# stompadapter_10-17-20.net
KiCad netlist of a schematic drawn in EAGLE
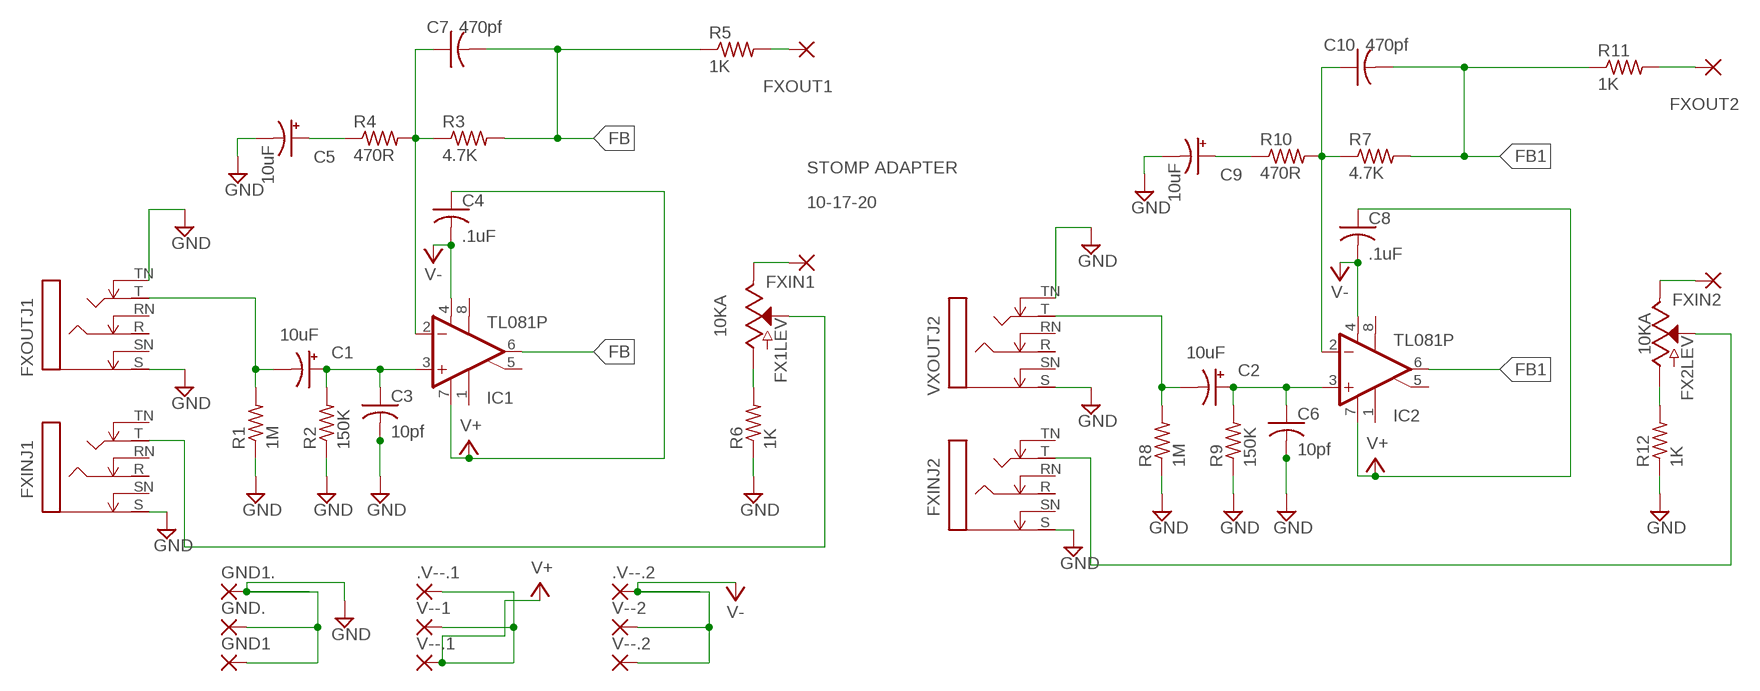
[diagram p0: schematic, sheet 1]

(export (version "E")
  (design (tool "Eeschema 10.0.6"))
  (components
    (comp (ref ".V--.1")
      (value "3,17/1,3")
      (footprint "eagle-import:3,17_1,3")
      (libsource (lib "eagle-import") (part "3,17/1,3"))
    )
    (comp (ref ".V--.2")
      (value "3,17/1,3")
      (footprint "eagle-import:3,17_1,3")
      (libsource (lib "eagle-import") (part "3,17/1,3"))
    )
    (comp (ref "C1")
      (value "10uF")
      (footprint "eagle-import:E5-6")
      (libsource (lib "eagle-import") (part "CPOL-USE5-6"))
    )
    (comp (ref "C2")
      (value "10uF")
      (footprint "eagle-import:E5-6")
      (libsource (lib "eagle-import") (part "CPOL-USE5-6"))
    )
    (comp (ref "C3")
      (value "10pf")
      (footprint "eagle-import:C050-025X075")
      (libsource (lib "eagle-import") (part "C-US050-025X075"))
    )
    (comp (ref "C4")
      (value ".1uF")
      (footprint "eagle-import:C025-025X050")
      (libsource (lib "eagle-import") (part "adafruit_420_C-US025-025X050"))
    )
    (comp (ref "C5")
      (value "10uF")
      (footprint "eagle-import:E5-6")
      (libsource (lib "eagle-import") (part "CPOL-USE5-6"))
    )
    (comp (ref "C6")
      (value "10pf")
      (footprint "eagle-import:C050-025X075")
      (libsource (lib "eagle-import") (part "C-US050-025X075"))
    )
    (comp (ref "C7")
      (value "470pf")
      (footprint "eagle-import:C050-025X075")
      (libsource (lib "eagle-import") (part "C-US050-025X075"))
    )
    (comp (ref "C8")
      (value ".1uF")
      (footprint "eagle-import:C025-025X050")
      (libsource (lib "eagle-import") (part "adafruit_420_C-US025-025X050"))
    )
    (comp (ref "C9")
      (value "10uF")
      (footprint "eagle-import:E5-6")
      (libsource (lib "eagle-import") (part "CPOL-USE5-6"))
    )
    (comp (ref "C10")
      (value "470pf")
      (footprint "eagle-import:C050-025X075")
      (libsource (lib "eagle-import") (part "C-US050-025X075"))
    )
    (comp (ref "FX1LEV")
      (value "10KA")
      (footprint "eagle-import:POT-PTH-ALPS-KIT")
      (libsource (lib "eagle-import") (part "POTENTIOMETER-PTH-9MM-1/20W-20%-KIT"))
    )
    (comp (ref "FX2LEV")
      (value "10KA")
      (footprint "eagle-import:POT-PTH-ALPS-KIT")
      (libsource (lib "eagle-import") (part "POTENTIOMETER-PTH-9MM-1/20W-20%-KIT"))
    )
    (comp (ref "FXIN1")
      (value "3,17/1,3")
      (footprint "eagle-import:3,17_1,3")
      (libsource (lib "eagle-import") (part "wirepad_412_3,17/1,3"))
    )
    (comp (ref "FXIN2")
      (value "3,17/1,3")
      (footprint "eagle-import:3,17_1,3")
      (libsource (lib "eagle-import") (part "wirepad_412_3,17/1,3"))
    )
    (comp (ref "FXINJ1")
      (value "NEUTRIXNMJ6HCD2")
      (footprint "eagle-import:NMJ6HCD2-LARGEPINS")
      (libsource (lib "eagle-import") (part "NEUTRIXNMJ6HCD2"))
    )
    (comp (ref "FXINJ2")
      (value "NEUTRIXNMJ6HCD2")
      (footprint "eagle-import:NMJ6HCD2-LARGEPINS")
      (libsource (lib "eagle-import") (part "NEUTRIXNMJ6HCD2"))
    )
    (comp (ref "FXOUT1")
      (value "3,17/1,3")
      (footprint "eagle-import:3,17_1,3")
      (libsource (lib "eagle-import") (part "wirepad_412_3,17/1,3"))
    )
    (comp (ref "FXOUT2")
      (value "3,17/1,3")
      (footprint "eagle-import:3,17_1,3")
      (libsource (lib "eagle-import") (part "wirepad_412_3,17/1,3"))
    )
    (comp (ref "FXOUTJ1")
      (value "NEUTRIXNMJ6HCD2")
      (footprint "eagle-import:NMJ6HCD2-LARGEPINS")
      (libsource (lib "eagle-import") (part "NEUTRIXNMJ6HCD2"))
    )
    (comp (ref "GND.")
      (value "3,17/1,3")
      (footprint "eagle-import:3,17_1,3")
      (libsource (lib "eagle-import") (part "3,17/1,3"))
    )
    (comp (ref "GND1")
      (value "3,17/1,3")
      (footprint "eagle-import:3,17_1,3")
      (libsource (lib "eagle-import") (part "3,17/1,3"))
    )
    (comp (ref "GND1.")
      (value "3,17/1,3")
      (footprint "eagle-import:3,17_1,3")
      (libsource (lib "eagle-import") (part "3,17/1,3"))
    )
    (comp (ref "IC1")
      (value "TL081P")
      (footprint "eagle-import:DIL08")
      (libsource (lib "eagle-import") (part "TL081P"))
    )
    (comp (ref "IC2")
      (value "TL081P")
      (footprint "eagle-import:DIL08")
      (libsource (lib "eagle-import") (part "TL081P"))
    )
    (comp (ref "R1")
      (value "1M")
      (footprint "eagle-import:0204_7")
      (libsource (lib "eagle-import") (part "R-US_0204/7"))
    )
    (comp (ref "R2")
      (value "150K")
      (footprint "eagle-import:0204_7")
      (libsource (lib "eagle-import") (part "R-US_0204/7"))
    )
    (comp (ref "R3")
      (value "4.7K")
      (footprint "eagle-import:0204_7")
      (libsource (lib "eagle-import") (part "R-US_0204/7"))
    )
    (comp (ref "R4")
      (value "470R")
      (footprint "eagle-import:0204_7")
      (libsource (lib "eagle-import") (part "R-US_0204/7"))
    )
    (comp (ref "R5")
      (value "1K")
      (footprint "eagle-import:0204_7")
      (libsource (lib "eagle-import") (part "R-US_0204/7"))
    )
    (comp (ref "R6")
      (value "1K")
      (footprint "eagle-import:0204_7")
      (libsource (lib "eagle-import") (part "R-US_0204/7"))
    )
    (comp (ref "R7")
      (value "4.7K")
      (footprint "eagle-import:0204_7")
      (libsource (lib "eagle-import") (part "R-US_0204/7"))
    )
    (comp (ref "R8")
      (value "1M")
      (footprint "eagle-import:0204_7")
      (libsource (lib "eagle-import") (part "R-US_0204/7"))
    )
    (comp (ref "R9")
      (value "150K")
      (footprint "eagle-import:0204_7")
      (libsource (lib "eagle-import") (part "R-US_0204/7"))
    )
    (comp (ref "R10")
      (value "470R")
      (footprint "eagle-import:0204_7")
      (libsource (lib "eagle-import") (part "R-US_0204/7"))
    )
    (comp (ref "R11")
      (value "1K")
      (footprint "eagle-import:0204_7")
      (libsource (lib "eagle-import") (part "R-US_0204/7"))
    )
    (comp (ref "R12")
      (value "1K")
      (footprint "eagle-import:0204_7")
      (libsource (lib "eagle-import") (part "R-US_0204/7"))
    )
    (comp (ref "V--.1")
      (value "3,17/1,3")
      (footprint "eagle-import:3,17_1,3")
      (libsource (lib "eagle-import") (part "3,17/1,3"))
    )
    (comp (ref "V--.2")
      (value "3,17/1,3")
      (footprint "eagle-import:3,17_1,3")
      (libsource (lib "eagle-import") (part "3,17/1,3"))
    )
    (comp (ref "V--1")
      (value "3,17/1,3")
      (footprint "eagle-import:3,17_1,3")
      (libsource (lib "eagle-import") (part "3,17/1,3"))
    )
    (comp (ref "V--2")
      (value "3,17/1,3")
      (footprint "eagle-import:3,17_1,3")
      (libsource (lib "eagle-import") (part "3,17/1,3"))
    )
    (comp (ref "VXOUTJ2")
      (value "NEUTRIXNMJ6HCD2")
      (footprint "eagle-import:NMJ6HCD2-LARGEPINS")
      (libsource (lib "eagle-import") (part "NEUTRIXNMJ6HCD2"))
    )
  )
  (nets
    (net (code "1") (name "FB") (class "Default")
      (node (ref "C7") (pin "2") (pinfunction "2_2") (pintype "passive"))
      (node (ref "IC1") (pin "6") (pinfunction "OUT_6") (pintype "output"))
      (node (ref "R3") (pin "2") (pinfunction "2_2") (pintype "passive"))
      (node (ref "R5") (pin "1") (pinfunction "1_1") (pintype "passive"))
    )
    (net (code "2") (name "FB1") (class "Default")
      (node (ref "C10") (pin "2") (pinfunction "2_2") (pintype "passive"))
      (node (ref "IC2") (pin "6") (pinfunction "OUT_6") (pintype "output"))
      (node (ref "R11") (pin "1") (pinfunction "1_1") (pintype "passive"))
      (node (ref "R7") (pin "2") (pinfunction "2_2") (pintype "passive"))
    )
    (net (code "3") (name "GND") (class "Default")
      (node (ref "C3") (pin "2") (pinfunction "2_2") (pintype "passive"))
      (node (ref "C5") (pin "-") (pinfunction "-_-") (pintype "passive"))
      (node (ref "C6") (pin "2") (pinfunction "2_2") (pintype "passive"))
      (node (ref "C9") (pin "-") (pinfunction "-_-") (pintype "passive"))
      (node (ref "FXINJ1") (pin "S") (pinfunction "S_S") (pintype "passive"))
      (node (ref "FXINJ2") (pin "S") (pinfunction "S_S") (pintype "passive"))
      (node (ref "FXOUTJ1") (pin "S") (pinfunction "S_S") (pintype "passive"))
      (node (ref "FXOUTJ1") (pin "TN") (pinfunction "TN_TN") (pintype "passive"))
      (node (ref "GND.") (pin "1") (pinfunction "P_1") (pintype "passive"))
      (node (ref "GND1") (pin "1") (pinfunction "P_1") (pintype "passive"))
      (node (ref "GND1.") (pin "1") (pinfunction "P_1") (pintype "passive"))
      (node (ref "R1") (pin "1") (pinfunction "1_1") (pintype "passive"))
      (node (ref "R12") (pin "1") (pinfunction "1_1") (pintype "passive"))
      (node (ref "R2") (pin "1") (pinfunction "1_1") (pintype "passive"))
      (node (ref "R6") (pin "1") (pinfunction "1_1") (pintype "passive"))
      (node (ref "R8") (pin "1") (pinfunction "1_1") (pintype "passive"))
      (node (ref "R9") (pin "1") (pinfunction "1_1") (pintype "passive"))
      (node (ref "VXOUTJ2") (pin "S") (pinfunction "S_S") (pintype "passive"))
      (node (ref "VXOUTJ2") (pin "TN") (pinfunction "TN_TN") (pintype "passive"))
    )
    (net (code "4") (name "Net-(C1-Pad-)") (class "Default")
      (node (ref "C1") (pin "-") (pinfunction "-_-") (pintype "passive"))
      (node (ref "FXOUTJ1") (pin "T") (pinfunction "T_T") (pintype "passive"))
      (node (ref "R1") (pin "2") (pinfunction "2_2") (pintype "passive"))
    )
    (net (code "5") (name "Net-(C2-Pad-)") (class "Default")
      (node (ref "C2") (pin "-") (pinfunction "-_-") (pintype "passive"))
      (node (ref "R8") (pin "2") (pinfunction "2_2") (pintype "passive"))
      (node (ref "VXOUTJ2") (pin "T") (pinfunction "T_T") (pintype "passive"))
    )
    (net (code "6") (name "Net-(C5-Pad+)") (class "Default")
      (node (ref "C5") (pin "+") (pinfunction "+_+") (pintype "passive"))
      (node (ref "R4") (pin "1") (pinfunction "1_1") (pintype "passive"))
    )
    (net (code "7") (name "Net-(C9-Pad+)") (class "Default")
      (node (ref "C9") (pin "+") (pinfunction "+_+") (pintype "passive"))
      (node (ref "R10") (pin "1") (pinfunction "1_1") (pintype "passive"))
    )
    (net (code "8") (name "Net-(FX1LEV-A)") (class "Default")
      (node (ref "FX1LEV") (pin "P$3") (pinfunction "A_P$3") (pintype "passive"))
      (node (ref "R6") (pin "2") (pinfunction "2_2") (pintype "passive"))
    )
    (net (code "9") (name "Net-(FX1LEV-E)") (class "Default")
      (node (ref "FX1LEV") (pin "P$1") (pinfunction "E_P$1") (pintype "passive"))
      (node (ref "FXIN1") (pin "1") (pinfunction "P_1") (pintype "passive"))
    )
    (net (code "10") (name "Net-(FX1LEV-S)") (class "Default")
      (node (ref "FX1LEV") (pin "P$2") (pinfunction "S_P$2") (pintype "passive"))
      (node (ref "FXINJ1") (pin "T") (pinfunction "T_T") (pintype "passive"))
    )
    (net (code "11") (name "Net-(FX2LEV-A)") (class "Default")
      (node (ref "FX2LEV") (pin "P$3") (pinfunction "A_P$3") (pintype "passive"))
      (node (ref "R12") (pin "2") (pinfunction "2_2") (pintype "passive"))
    )
    (net (code "12") (name "Net-(FX2LEV-E)") (class "Default")
      (node (ref "FX2LEV") (pin "P$1") (pinfunction "E_P$1") (pintype "passive"))
      (node (ref "FXIN2") (pin "1") (pinfunction "P_1") (pintype "passive"))
    )
    (net (code "13") (name "Net-(FX2LEV-S)") (class "Default")
      (node (ref "FX2LEV") (pin "P$2") (pinfunction "S_P$2") (pintype "passive"))
      (node (ref "FXINJ2") (pin "T") (pinfunction "T_T") (pintype "passive"))
    )
    (net (code "14") (name "Net-(FXOUT1-P)") (class "Default")
      (node (ref "FXOUT1") (pin "1") (pinfunction "P_1") (pintype "passive"))
      (node (ref "R5") (pin "2") (pinfunction "2_2") (pintype "passive"))
    )
    (net (code "15") (name "Net-(FXOUT2-P)") (class "Default")
      (node (ref "FXOUT2") (pin "1") (pinfunction "P_1") (pintype "passive"))
      (node (ref "R11") (pin "2") (pinfunction "2_2") (pintype "passive"))
    )
    (net (code "16") (name "Net-(IC1-+IN)") (class "Default")
      (node (ref "C1") (pin "+") (pinfunction "+_+") (pintype "passive"))
      (node (ref "C3") (pin "1") (pinfunction "1_1") (pintype "passive"))
      (node (ref "IC1") (pin "3") (pinfunction "+IN_3") (pintype "input"))
      (node (ref "R2") (pin "2") (pinfunction "2_2") (pintype "passive"))
    )
    (net (code "17") (name "Net-(IC1--IN)") (class "Default")
      (node (ref "C7") (pin "1") (pinfunction "1_1") (pintype "passive"))
      (node (ref "IC1") (pin "2") (pinfunction "-IN_2") (pintype "input"))
      (node (ref "R3") (pin "1") (pinfunction "1_1") (pintype "passive"))
      (node (ref "R4") (pin "2") (pinfunction "2_2") (pintype "passive"))
    )
    (net (code "18") (name "Net-(IC2-+IN)") (class "Default")
      (node (ref "C2") (pin "+") (pinfunction "+_+") (pintype "passive"))
      (node (ref "C6") (pin "1") (pinfunction "1_1") (pintype "passive"))
      (node (ref "IC2") (pin "3") (pinfunction "+IN_3") (pintype "input"))
      (node (ref "R9") (pin "2") (pinfunction "2_2") (pintype "passive"))
    )
    (net (code "19") (name "Net-(IC2--IN)") (class "Default")
      (node (ref "C10") (pin "1") (pinfunction "1_1") (pintype "passive"))
      (node (ref "IC2") (pin "2") (pinfunction "-IN_2") (pintype "input"))
      (node (ref "R10") (pin "2") (pinfunction "2_2") (pintype "passive"))
      (node (ref "R7") (pin "1") (pinfunction "1_1") (pintype "passive"))
    )
    (net (code "20") (name "V+") (class "Default")
      (node (ref ".V--.1") (pin "1") (pinfunction "P_1") (pintype "passive"))
      (node (ref "C4") (pin "1") (pinfunction "1_1") (pintype "passive"))
      (node (ref "C8") (pin "1") (pinfunction "1_1") (pintype "passive"))
      (node (ref "IC1") (pin "7") (pinfunction "V+_7") (pintype "power_in"))
      (node (ref "IC2") (pin "7") (pinfunction "V+_7") (pintype "power_in"))
      (node (ref "V--.1") (pin "1") (pinfunction "P_1") (pintype "passive"))
      (node (ref "V--1") (pin "1") (pinfunction "P_1") (pintype "passive"))
    )
    (net (code "21") (name "V-") (class "Default")
      (node (ref ".V--.2") (pin "1") (pinfunction "P_1") (pintype "passive"))
      (node (ref "C4") (pin "2") (pinfunction "2_2") (pintype "passive"))
      (node (ref "C8") (pin "2") (pinfunction "2_2") (pintype "passive"))
      (node (ref "IC1") (pin "4") (pinfunction "V-_4") (pintype "power_in"))
      (node (ref "IC2") (pin "4") (pinfunction "V-_4") (pintype "power_in"))
      (node (ref "V--.2") (pin "1") (pinfunction "P_1") (pintype "passive"))
      (node (ref "V--2") (pin "1") (pinfunction "P_1") (pintype "passive"))
    )
    (net (code "22") (name "unconnected-(FXINJ1-PadR)") (class "Default")
      (node (ref "FXINJ1") (pin "R") (pinfunction "R_R") (pintype "passive"))
    )
    (net (code "23") (name "unconnected-(FXINJ1-PadRN)") (class "Default")
      (node (ref "FXINJ1") (pin "RN") (pinfunction "RN_RN") (pintype "passive"))
    )
    (net (code "24") (name "unconnected-(FXINJ1-PadSN)") (class "Default")
      (node (ref "FXINJ1") (pin "SN") (pinfunction "SN_SN") (pintype "passive"))
    )
    (net (code "25") (name "unconnected-(FXINJ1-PadTN)") (class "Default")
      (node (ref "FXINJ1") (pin "TN") (pinfunction "TN_TN") (pintype "passive"))
    )
    (net (code "26") (name "unconnected-(FXINJ2-PadR)") (class "Default")
      (node (ref "FXINJ2") (pin "R") (pinfunction "R_R") (pintype "passive"))
    )
    (net (code "27") (name "unconnected-(FXINJ2-PadRN)") (class "Default")
      (node (ref "FXINJ2") (pin "RN") (pinfunction "RN_RN") (pintype "passive"))
    )
    (net (code "28") (name "unconnected-(FXINJ2-PadSN)") (class "Default")
      (node (ref "FXINJ2") (pin "SN") (pinfunction "SN_SN") (pintype "passive"))
    )
    (net (code "29") (name "unconnected-(FXINJ2-PadTN)") (class "Default")
      (node (ref "FXINJ2") (pin "TN") (pinfunction "TN_TN") (pintype "passive"))
    )
    (net (code "30") (name "unconnected-(FXOUTJ1-PadR)") (class "Default")
      (node (ref "FXOUTJ1") (pin "R") (pinfunction "R_R") (pintype "passive"))
    )
    (net (code "31") (name "unconnected-(FXOUTJ1-PadRN)") (class "Default")
      (node (ref "FXOUTJ1") (pin "RN") (pinfunction "RN_RN") (pintype "passive"))
    )
    (net (code "32") (name "unconnected-(FXOUTJ1-PadSN)") (class "Default")
      (node (ref "FXOUTJ1") (pin "SN") (pinfunction "SN_SN") (pintype "passive"))
    )
    (net (code "33") (name "unconnected-(IC1-ON1-Pad1)") (class "Default")
      (node (ref "IC1") (pin "1") (pinfunction "ON1_1") (pintype "passive"))
    )
    (net (code "34") (name "unconnected-(IC1-ON2-Pad5)") (class "Default")
      (node (ref "IC1") (pin "5") (pinfunction "ON2_5") (pintype "passive"))
    )
    (net (code "35") (name "unconnected-(IC1-OPT-Pad8)") (class "Default")
      (node (ref "IC1") (pin "8") (pinfunction "OPT_8") (pintype "passive"))
    )
    (net (code "36") (name "unconnected-(IC2-ON1-Pad1)") (class "Default")
      (node (ref "IC2") (pin "1") (pinfunction "ON1_1") (pintype "passive"))
    )
    (net (code "37") (name "unconnected-(IC2-ON2-Pad5)") (class "Default")
      (node (ref "IC2") (pin "5") (pinfunction "ON2_5") (pintype "passive"))
    )
    (net (code "38") (name "unconnected-(IC2-OPT-Pad8)") (class "Default")
      (node (ref "IC2") (pin "8") (pinfunction "OPT_8") (pintype "passive"))
    )
    (net (code "39") (name "unconnected-(VXOUTJ2-PadR)") (class "Default")
      (node (ref "VXOUTJ2") (pin "R") (pinfunction "R_R") (pintype "passive"))
    )
    (net (code "40") (name "unconnected-(VXOUTJ2-PadRN)") (class "Default")
      (node (ref "VXOUTJ2") (pin "RN") (pinfunction "RN_RN") (pintype "passive"))
    )
    (net (code "41") (name "unconnected-(VXOUTJ2-PadSN)") (class "Default")
      (node (ref "VXOUTJ2") (pin "SN") (pinfunction "SN_SN") (pintype "passive"))
    )
  )
)
